# vest-ctrl.net
KiCad netlist of a schematic drawn in EAGLE
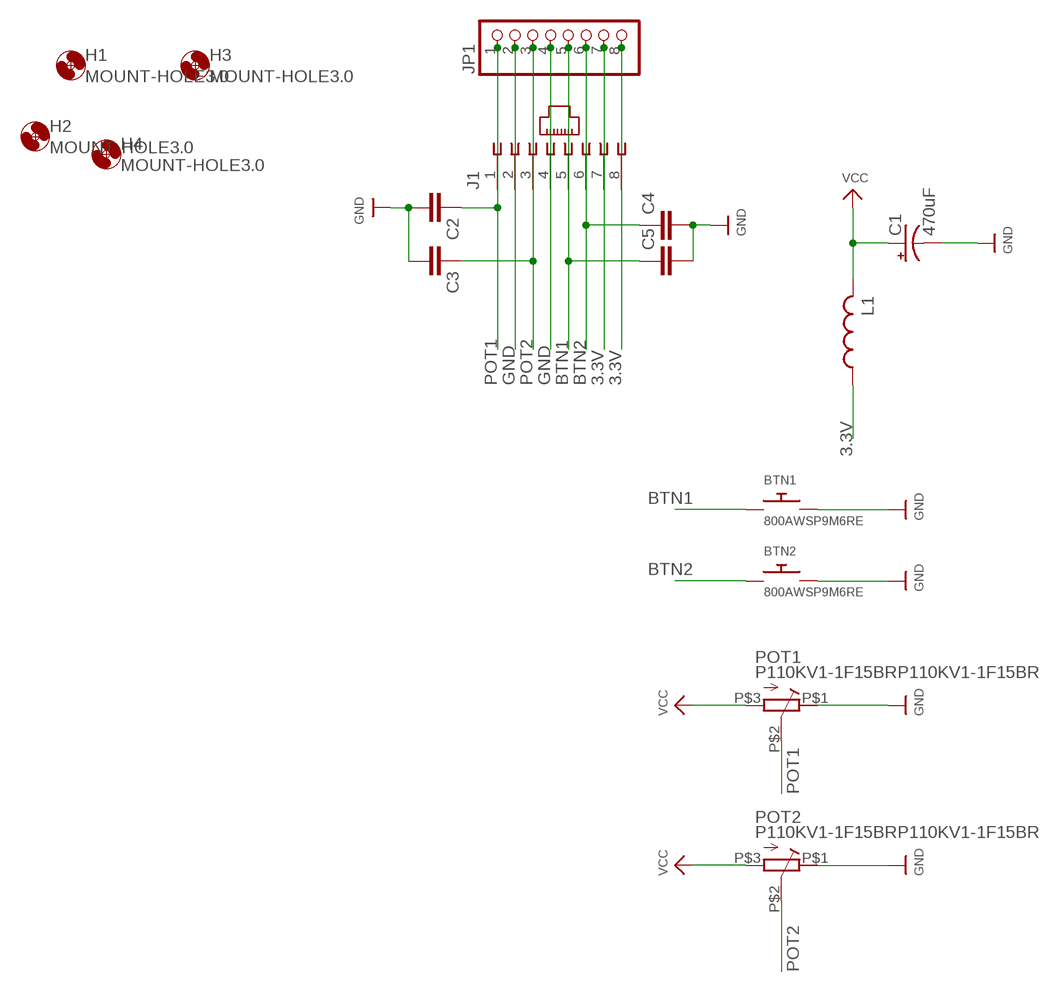
[diagram p0: schematic, sheet 1]

(export (version "E")
  (design (tool "Eeschema 10.0.6"))
  (components
    (comp (ref "BTN1")
      (value "800AWSP9M6RE")
      (footprint "eagle-import:800AWSP9M6RE")
      (libsource (lib "eagle-import") (part "800AWSP9M6RE"))
    )
    (comp (ref "BTN2")
      (value "800AWSP9M6RE")
      (footprint "eagle-import:800AWSP9M6RE")
      (libsource (lib "eagle-import") (part "800AWSP9M6RE"))
    )
    (comp (ref "C1")
      (value "470uF")
      (footprint "eagle-import:TT2D5L")
      (libsource (lib "eagle-import") (part "CPOL-USTT2D5L"))
    )
    (comp (ref "C2")
      (value "C-EU025-025X050")
      (footprint "eagle-import:C025-025X050")
      (libsource (lib "eagle-import") (part "C-EU025-025X050"))
    )
    (comp (ref "C3")
      (value "C-EU025-025X050")
      (footprint "eagle-import:C025-025X050")
      (libsource (lib "eagle-import") (part "C-EU025-025X050"))
    )
    (comp (ref "C4")
      (value "C-EU025-025X050")
      (footprint "eagle-import:C025-025X050")
      (libsource (lib "eagle-import") (part "C-EU025-025X050"))
    )
    (comp (ref "C5")
      (value "C-EU025-025X050")
      (footprint "eagle-import:C025-025X050")
      (libsource (lib "eagle-import") (part "C-EU025-025X050"))
    )
    (comp (ref "H1")
      (value "MOUNT-HOLE3.0")
      (footprint "eagle-import:3,0")
      (libsource (lib "eagle-import") (part "MOUNT-HOLE3.0"))
    )
    (comp (ref "H2")
      (value "MOUNT-HOLE3.0")
      (footprint "eagle-import:3,0")
      (libsource (lib "eagle-import") (part "MOUNT-HOLE3.0"))
    )
    (comp (ref "H3")
      (value "MOUNT-HOLE3.0")
      (footprint "eagle-import:3,0")
      (libsource (lib "eagle-import") (part "MOUNT-HOLE3.0"))
    )
    (comp (ref "H4")
      (value "MOUNT-HOLE3.0")
      (footprint "eagle-import:3,0")
      (libsource (lib "eagle-import") (part "MOUNT-HOLE3.0"))
    )
    (comp (ref "J1")
      (value "215877-4")
      (footprint "eagle-import:215877-4")
      (libsource (lib "eagle-import") (part "215877-4"))
    )
    (comp (ref "JP1")
      (value "HEADER-1X870MIL")
      (footprint "eagle-import:1X08_ROUND_70")
      (libsource (lib "eagle-import") (part "HEADER-1X870MIL"))
    )
    (comp (ref "L1")
      (value "L-US0207/10")
      (footprint "eagle-import:0207_10")
      (libsource (lib "eagle-import") (part "L-US0207/10"))
    )
    (comp (ref "POT1")
      (value "P110KV1-1F15BRP110KV1-1F15BR")
      (footprint "eagle-import:P110KV1-1F15BR")
      (libsource (lib "eagle-import") (part "P110KV1-1F15BRP110KV1-1F15BR"))
    )
    (comp (ref "POT2")
      (value "P110KV1-1F15BRP110KV1-1F15BR")
      (footprint "eagle-import:P110KV1-1F15BR")
      (libsource (lib "eagle-import") (part "P110KV1-1F15BRP110KV1-1F15BR"))
    )
  )
  (nets
    (net (code "1") (name "/3.3V") (class "Default")
      (node (ref "J1") (pin "7") (pinfunction "7_7") (pintype "passive"))
      (node (ref "J1") (pin "8") (pinfunction "8_8") (pintype "passive"))
      (node (ref "JP1") (pin "7") (pinfunction "7_7") (pintype "passive"))
      (node (ref "JP1") (pin "8") (pinfunction "8_8") (pintype "passive"))
      (node (ref "L1") (pin "1") (pinfunction "1_1") (pintype "passive"))
    )
    (net (code "2") (name "/BTN1") (class "Default")
      (node (ref "BTN1") (pin "SW1") (pinfunction "P$1_SW1") (pintype "passive"))
      (node (ref "C5") (pin "1") (pinfunction "1_1") (pintype "passive"))
      (node (ref "J1") (pin "5") (pinfunction "5_5") (pintype "passive"))
      (node (ref "JP1") (pin "5") (pinfunction "5_5") (pintype "passive"))
    )
    (net (code "3") (name "/BTN2") (class "Default")
      (node (ref "BTN2") (pin "SW1") (pinfunction "P$1_SW1") (pintype "passive"))
      (node (ref "C4") (pin "1") (pinfunction "1_1") (pintype "passive"))
      (node (ref "J1") (pin "6") (pinfunction "6_6") (pintype "passive"))
      (node (ref "JP1") (pin "6") (pinfunction "6_6") (pintype "passive"))
    )
    (net (code "4") (name "/POT1") (class "Default")
      (node (ref "C2") (pin "1") (pinfunction "1_1") (pintype "passive"))
      (node (ref "J1") (pin "1") (pinfunction "1_1") (pintype "passive"))
      (node (ref "JP1") (pin "1") (pinfunction "1_1") (pintype "passive"))
      (node (ref "POT1") (pin "P$2") (pinfunction "S_P$2") (pintype "passive"))
    )
    (net (code "5") (name "/POT2") (class "Default")
      (node (ref "C3") (pin "1") (pinfunction "1_1") (pintype "passive"))
      (node (ref "J1") (pin "3") (pinfunction "3_3") (pintype "passive"))
      (node (ref "JP1") (pin "3") (pinfunction "3_3") (pintype "passive"))
      (node (ref "POT2") (pin "P$2") (pinfunction "S_P$2") (pintype "passive"))
    )
    (net (code "6") (name "GND") (class "Default")
      (node (ref "BTN1") (pin "SW2") (pinfunction "P$2_SW2") (pintype "passive"))
      (node (ref "BTN2") (pin "SW2") (pinfunction "P$2_SW2") (pintype "passive"))
      (node (ref "C1") (pin "-") (pinfunction "-_-") (pintype "passive"))
      (node (ref "C2") (pin "2") (pinfunction "2_2") (pintype "passive"))
      (node (ref "C3") (pin "2") (pinfunction "2_2") (pintype "passive"))
      (node (ref "C4") (pin "2") (pinfunction "2_2") (pintype "passive"))
      (node (ref "C5") (pin "2") (pinfunction "2_2") (pintype "passive"))
      (node (ref "J1") (pin "2") (pinfunction "2_2") (pintype "passive"))
      (node (ref "J1") (pin "4") (pinfunction "4_4") (pintype "passive"))
      (node (ref "JP1") (pin "2") (pinfunction "2_2") (pintype "passive"))
      (node (ref "JP1") (pin "4") (pinfunction "4_4") (pintype "passive"))
      (node (ref "POT1") (pin "P$1") (pinfunction "A_P$1") (pintype "passive"))
      (node (ref "POT2") (pin "P$1") (pinfunction "A_P$1") (pintype "passive"))
    )
    (net (code "7") (name "VCC") (class "Default")
      (node (ref "C1") (pin "+") (pinfunction "+_+") (pintype "passive"))
      (node (ref "L1") (pin "2") (pinfunction "2_2") (pintype "passive"))
      (node (ref "POT1") (pin "P$3") (pinfunction "E_P$3") (pintype "passive"))
      (node (ref "POT2") (pin "P$3") (pinfunction "E_P$3") (pintype "passive"))
    )
  )
)
